# pico_host_board_top.net
KiCad netlist of a schematic drawn in Altium Designer
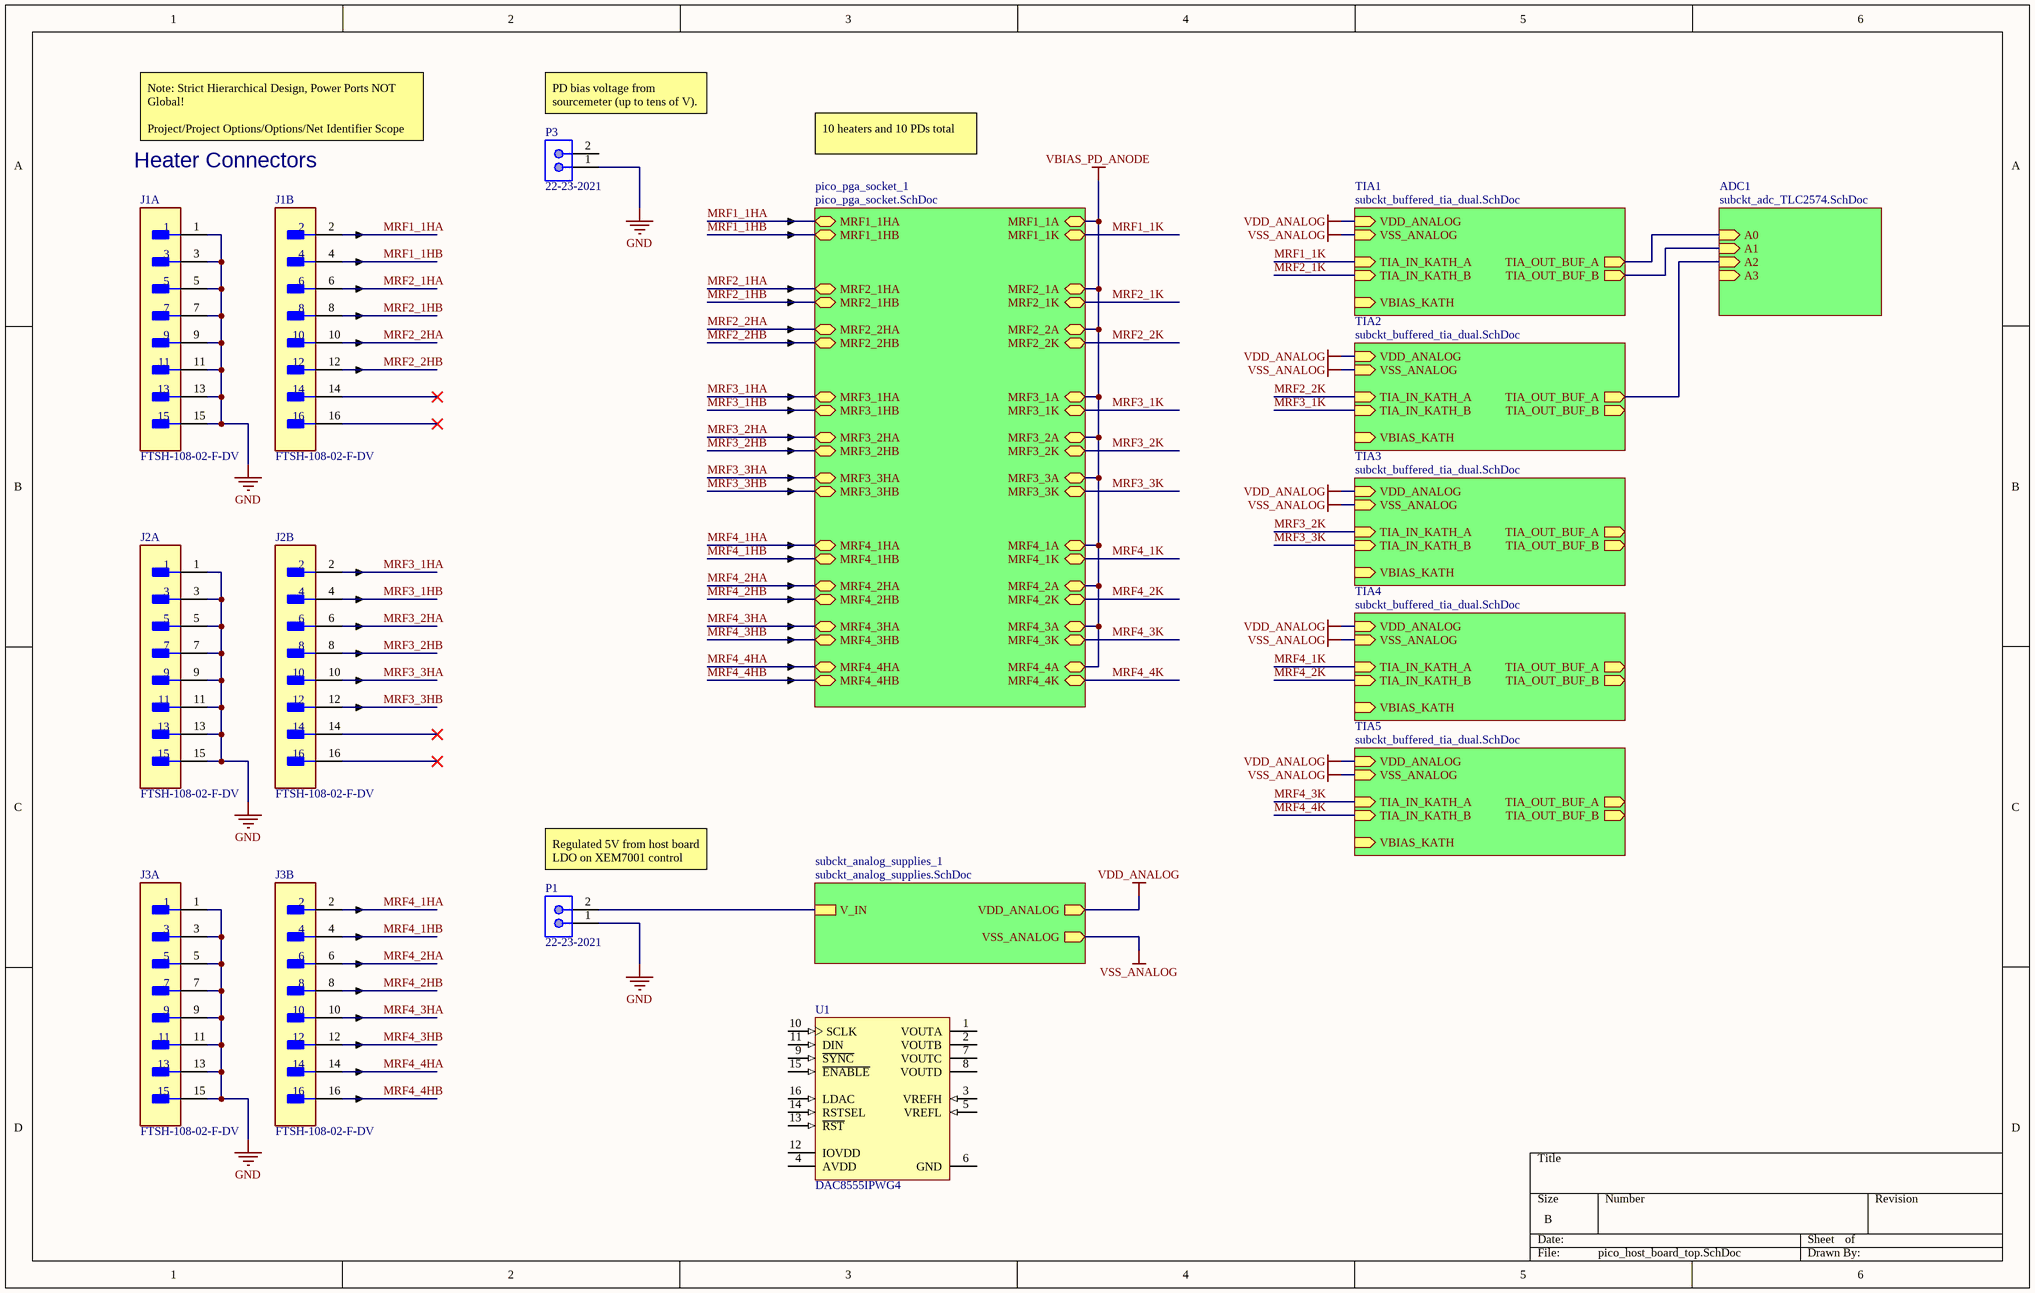
[diagram p0: pico_host_board_top.SchDoc]

(export (version "E")
  (design (tool "Eeschema 10.0.6"))
  (components
    (comp (ref "J1")
      (value "FTSH-108-02-F-DV")
      (footprint "LIBRARYSOURCE=Vault¦VAULTGUID=B7D15EC3-160A-466F-A46C-7801FE6295A7¦REVISIONGUID=4386816A-B426-492F-A73C-09950B70C106¦FOOTPRINT=FP-FTSH-108-02-F-DV")
      (description "CONN HEADER SMD 16POS 1.27MM")
      (fields
        (field (name "OCTOPART") "https://octopart.com/ftsh-108-02-f-dv-samtec-10605893")
        (field (name "MANUFACTURER") "Samtec")
      )
      (libsource (lib "SMT_header_FTSH") (part "FP-FTSH-108-02-F-DV"))
    )
    (comp (ref "J2")
      (value "FTSH-108-02-F-DV")
      (footprint "LIBRARYSOURCE=Vault¦VAULTGUID=B7D15EC3-160A-466F-A46C-7801FE6295A7¦REVISIONGUID=4386816A-B426-492F-A73C-09950B70C106¦FOOTPRINT=FP-FTSH-108-02-F-DV")
      (description "CONN HEADER SMD 16POS 1.27MM")
      (fields
        (field (name "OCTOPART") "https://octopart.com/ftsh-108-02-f-dv-samtec-10605893")
        (field (name "MANUFACTURER") "Samtec")
      )
      (libsource (lib "SMT_header_FTSH") (part "FP-FTSH-108-02-F-DV"))
    )
    (comp (ref "J3")
      (value "FTSH-108-02-F-DV")
      (footprint "LIBRARYSOURCE=Vault¦VAULTGUID=B7D15EC3-160A-466F-A46C-7801FE6295A7¦REVISIONGUID=4386816A-B426-492F-A73C-09950B70C106¦FOOTPRINT=FP-FTSH-108-02-F-DV")
      (description "CONN HEADER SMD 16POS 1.27MM")
      (fields
        (field (name "OCTOPART") "https://octopart.com/ftsh-108-02-f-dv-samtec-10605893")
        (field (name "MANUFACTURER") "Samtec")
      )
      (libsource (lib "SMT_header_FTSH") (part "FP-FTSH-108-02-F-DV"))
    )
    (comp (ref "P1")
      (value "22-23-2021")
      (footprint "MOLX-22-23-2021_V")
      (libsource (lib "Altium Content Vault") (part "CN-1P-M-R2"))
    )
    (comp (ref "P3")
      (value "22-23-2021")
      (footprint "MOLX-22-23-2021_V")
      (libsource (lib "Altium Content Vault") (part "CN-1P-M-R2"))
    )
    (comp (ref "U1")
      (value "DAC8555IPWG4")
      (footprint "TI-PW16_L")
      (fields (field (name "MANUFACTURER") "Texas Instruments"))
      (libsource (lib "Altium Content Vault") (part "TI-DAC8555PW16"))
    )
  )
  (nets
    (net (code "2") (name "/MRF1_1HA") (class "Default")
      (node (ref "J1") (pin "2") (pinfunction "2_2") (pintype "passive"))
    )
    (net (code "3") (name "/MRF1_1HB") (class "Default")
      (node (ref "J1") (pin "4") (pinfunction "4_4") (pintype "passive"))
    )
    (net (code "5") (name "/MRF2_1HA") (class "Default")
      (node (ref "J1") (pin "6") (pinfunction "6_6") (pintype "passive"))
    )
    (net (code "6") (name "/MRF2_1HB") (class "Default")
      (node (ref "J1") (pin "8") (pinfunction "8_8") (pintype "passive"))
    )
    (net (code "8") (name "/MRF2_2HA") (class "Default")
      (node (ref "J1") (pin "10") (pinfunction "10_10") (pintype "passive"))
    )
    (net (code "9") (name "/MRF2_2HB") (class "Default")
      (node (ref "J1") (pin "12") (pinfunction "12_12") (pintype "passive"))
    )
    (net (code "11") (name "/MRF3_1HA") (class "Default")
      (node (ref "J2") (pin "2") (pinfunction "2_2") (pintype "passive"))
    )
    (net (code "12") (name "/MRF3_1HB") (class "Default")
      (node (ref "J2") (pin "4") (pinfunction "4_4") (pintype "passive"))
    )
    (net (code "14") (name "/MRF3_2HA") (class "Default")
      (node (ref "J2") (pin "6") (pinfunction "6_6") (pintype "passive"))
    )
    (net (code "15") (name "/MRF3_2HB") (class "Default")
      (node (ref "J2") (pin "8") (pinfunction "8_8") (pintype "passive"))
    )
    (net (code "17") (name "/MRF3_3HA") (class "Default")
      (node (ref "J2") (pin "10") (pinfunction "10_10") (pintype "passive"))
    )
    (net (code "18") (name "/MRF3_3HB") (class "Default")
      (node (ref "J2") (pin "12") (pinfunction "12_12") (pintype "passive"))
    )
    (net (code "20") (name "/MRF4_1HA") (class "Default")
      (node (ref "J3") (pin "2") (pinfunction "2_2") (pintype "passive"))
    )
    (net (code "21") (name "/MRF4_1HB") (class "Default")
      (node (ref "J3") (pin "4") (pinfunction "4_4") (pintype "passive"))
    )
    (net (code "23") (name "/MRF4_2HA") (class "Default")
      (node (ref "J3") (pin "6") (pinfunction "6_6") (pintype "passive"))
    )
    (net (code "24") (name "/MRF4_2HB") (class "Default")
      (node (ref "J3") (pin "8") (pinfunction "8_8") (pintype "passive"))
    )
    (net (code "26") (name "/MRF4_3HA") (class "Default")
      (node (ref "J3") (pin "10") (pinfunction "10_10") (pintype "passive"))
    )
    (net (code "27") (name "/MRF4_3HB") (class "Default")
      (node (ref "J3") (pin "12") (pinfunction "12_12") (pintype "passive"))
    )
    (net (code "29") (name "/MRF4_4HA") (class "Default")
      (node (ref "J3") (pin "14") (pinfunction "14_14") (pintype "passive"))
    )
    (net (code "30") (name "/MRF4_4HB") (class "Default")
      (node (ref "J3") (pin "16") (pinfunction "16_16") (pintype "passive"))
    )
    (net (code "47") (name "/V_IN") (class "Default")
      (node (ref "P1") (pin "2") (pinfunction "2_2") (pintype "passive"))
    )
    (net (code "48") (name "GND") (class "Default")
      (node (ref "J1") (pin "1") (pinfunction "1_1") (pintype "passive"))
      (node (ref "J1") (pin "11") (pinfunction "11_11") (pintype "passive"))
      (node (ref "J1") (pin "13") (pinfunction "13_13") (pintype "passive"))
      (node (ref "J1") (pin "15") (pinfunction "15_15") (pintype "passive"))
      (node (ref "J1") (pin "3") (pinfunction "3_3") (pintype "passive"))
      (node (ref "J1") (pin "5") (pinfunction "5_5") (pintype "passive"))
      (node (ref "J1") (pin "7") (pinfunction "7_7") (pintype "passive"))
      (node (ref "J1") (pin "9") (pinfunction "9_9") (pintype "passive"))
      (node (ref "J2") (pin "1") (pinfunction "1_1") (pintype "passive"))
      (node (ref "J2") (pin "11") (pinfunction "11_11") (pintype "passive"))
      (node (ref "J2") (pin "13") (pinfunction "13_13") (pintype "passive"))
      (node (ref "J2") (pin "15") (pinfunction "15_15") (pintype "passive"))
      (node (ref "J2") (pin "3") (pinfunction "3_3") (pintype "passive"))
      (node (ref "J2") (pin "5") (pinfunction "5_5") (pintype "passive"))
      (node (ref "J2") (pin "7") (pinfunction "7_7") (pintype "passive"))
      (node (ref "J2") (pin "9") (pinfunction "9_9") (pintype "passive"))
      (node (ref "J3") (pin "1") (pinfunction "1_1") (pintype "passive"))
      (node (ref "J3") (pin "11") (pinfunction "11_11") (pintype "passive"))
      (node (ref "J3") (pin "13") (pinfunction "13_13") (pintype "passive"))
      (node (ref "J3") (pin "15") (pinfunction "15_15") (pintype "passive"))
      (node (ref "J3") (pin "3") (pinfunction "3_3") (pintype "passive"))
      (node (ref "J3") (pin "5") (pinfunction "5_5") (pintype "passive"))
      (node (ref "J3") (pin "7") (pinfunction "7_7") (pintype "passive"))
      (node (ref "J3") (pin "9") (pinfunction "9_9") (pintype "passive"))
      (node (ref "P1") (pin "1") (pinfunction "1_1") (pintype "passive"))
      (node (ref "P3") (pin "1") (pinfunction "1_1") (pintype "passive"))
    )
    (net (code "52") (name "unconnected-(J1-Pad14)") (class "Default")
      (node (ref "J1") (pin "14") (pinfunction "14_14") (pintype "passive+no_connect"))
    )
    (net (code "53") (name "unconnected-(J1-Pad16)") (class "Default")
      (node (ref "J1") (pin "16") (pinfunction "16_16") (pintype "passive+no_connect"))
    )
    (net (code "54") (name "unconnected-(J2-Pad14)") (class "Default")
      (node (ref "J2") (pin "14") (pinfunction "14_14") (pintype "passive+no_connect"))
    )
    (net (code "55") (name "unconnected-(J2-Pad16)") (class "Default")
      (node (ref "J2") (pin "16") (pinfunction "16_16") (pintype "passive+no_connect"))
    )
    (net (code "56") (name "unconnected-(P3-Pad2)") (class "Default")
      (node (ref "P3") (pin "2") (pinfunction "2_2") (pintype "passive"))
    )
    (net (code "57") (name "unconnected-(U1-AVDD-Pad4)") (class "Default")
      (node (ref "U1") (pin "4") (pinfunction "AVDD_4") (pintype "power_in"))
    )
    (net (code "58") (name "unconnected-(U1-DIN-Pad11)") (class "Default")
      (node (ref "U1") (pin "11") (pinfunction "DIN_11") (pintype "input"))
    )
    (net (code "59") (name "unconnected-(U1-GND-Pad6)") (class "Default")
      (node (ref "U1") (pin "6") (pinfunction "GND_6") (pintype "power_in"))
    )
    (net (code "60") (name "unconnected-(U1-IOVDD-Pad12)") (class "Default")
      (node (ref "U1") (pin "12") (pinfunction "IOVDD_12") (pintype "power_in"))
    )
    (net (code "61") (name "unconnected-(U1-LDAC-Pad16)") (class "Default")
      (node (ref "U1") (pin "16") (pinfunction "LDAC_16") (pintype "input"))
    )
    (net (code "62") (name "unconnected-(U1-RSTSEL-Pad14)") (class "Default")
      (node (ref "U1") (pin "14") (pinfunction "RSTSEL_14") (pintype "input"))
    )
    (net (code "63") (name "unconnected-(U1-SCLK-Pad10)") (class "Default")
      (node (ref "U1") (pin "10") (pinfunction "SCLK_10") (pintype "input"))
    )
    (net (code "64") (name "unconnected-(U1-VOUTA-Pad1)") (class "Default")
      (node (ref "U1") (pin "1") (pinfunction "VOUTA_1") (pintype "tri_state"))
    )
    (net (code "65") (name "unconnected-(U1-VOUTB-Pad2)") (class "Default")
      (node (ref "U1") (pin "2") (pinfunction "VOUTB_2") (pintype "tri_state"))
    )
    (net (code "66") (name "unconnected-(U1-VOUTC-Pad7)") (class "Default")
      (node (ref "U1") (pin "7") (pinfunction "VOUTC_7") (pintype "tri_state"))
    )
    (net (code "67") (name "unconnected-(U1-VOUTD-Pad8)") (class "Default")
      (node (ref "U1") (pin "8") (pinfunction "VOUTD_8") (pintype "tri_state"))
    )
    (net (code "68") (name "unconnected-(U1-VREFH-Pad3)") (class "Default")
      (node (ref "U1") (pin "3") (pinfunction "VREFH_3") (pintype "input"))
    )
    (net (code "69") (name "unconnected-(U1-VREFL-Pad5)") (class "Default")
      (node (ref "U1") (pin "5") (pinfunction "VREFL_5") (pintype "input"))
    )
    (net (code "70") (name "unconnected-(U1-~{ENABLE}-Pad15)") (class "Default")
      (node (ref "U1") (pin "15") (pinfunction "~{ENABLE}_15") (pintype "input"))
    )
    (net (code "71") (name "unconnected-(U1-~{RST}-Pad13)") (class "Default")
      (node (ref "U1") (pin "13") (pinfunction "~{RST}_13") (pintype "input"))
    )
    (net (code "72") (name "unconnected-(U1-~{SYNC}-Pad9)") (class "Default")
      (node (ref "U1") (pin "9") (pinfunction "~{SYNC}_9") (pintype "input"))
    )
  )
)
